# gps_and_sensor_20180111.net
KiCad netlist of a schematic drawn in EAGLE
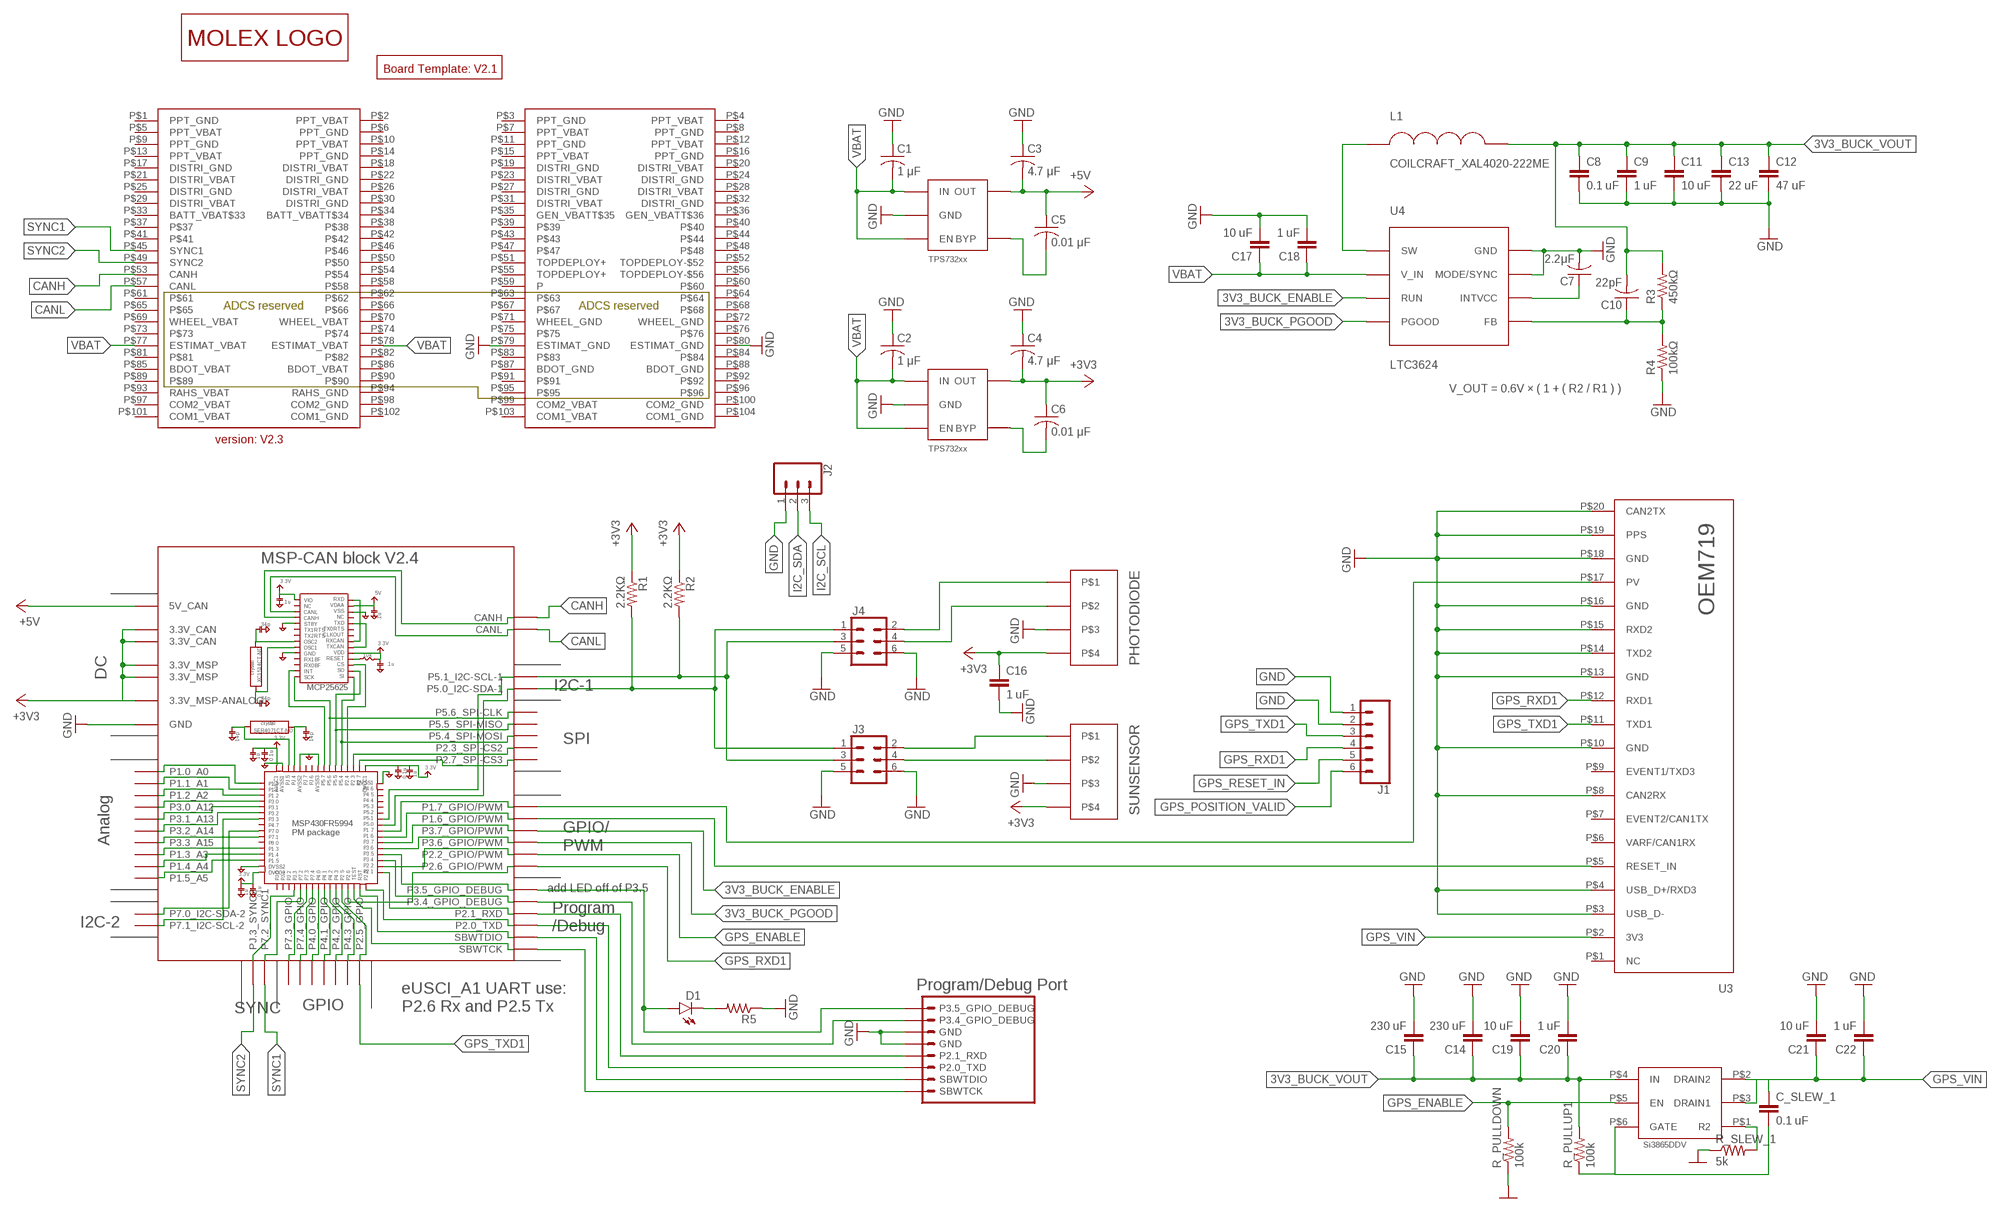
[diagram p0: schematic, sheet 1]

(export (version "E")
  (design (tool "Eeschema 10.0.6"))
  (components
    (comp (ref "B1")
      (value "BOARD_TEMPLATE1")
      (footprint "eagle-import:BOARD_TEMPLATE")
      (libsource (lib "eagle-import") (part "BOARD_TEMPLATE1"))
    )
    (comp (ref "BLK1")
      (value "MSP-CAN_BLOCK")
      (footprint "eagle-import:MSP-CAN_BLOCK")
      (libsource (lib "eagle-import") (part "MSP-CAN_BLOCK"))
    )
    (comp (ref "C1")
      (value "1 μF")
      (footprint "eagle-import:C0805")
      (libsource (lib "eagle-import") (part "C-USC0805"))
    )
    (comp (ref "C2")
      (value "1 μF")
      (footprint "eagle-import:C0805")
      (libsource (lib "eagle-import") (part "C-USC0805"))
    )
    (comp (ref "C3")
      (value "4.7 μF")
      (footprint "eagle-import:C0805")
      (libsource (lib "eagle-import") (part "C-USC0805"))
    )
    (comp (ref "C4")
      (value "4.7 μF")
      (footprint "eagle-import:C0805")
      (libsource (lib "eagle-import") (part "C-USC0805"))
    )
    (comp (ref "C5")
      (value "0.01 μF")
      (footprint "eagle-import:C0805")
      (libsource (lib "eagle-import") (part "C-USC0805"))
    )
    (comp (ref "C6")
      (value "0.01 μF")
      (footprint "eagle-import:C0805")
      (libsource (lib "eagle-import") (part "C-USC0805"))
    )
    (comp (ref "C7")
      (value "2.2μF")
      (footprint "eagle-import:C0805")
      (libsource (lib "eagle-import") (part "C-USC0805"))
    )
    (comp (ref "C8")
      (value "0.1 uF")
      (footprint "eagle-import:0805")
      (libsource (lib "eagle-import") (part "CAPACITOR0805"))
    )
    (comp (ref "C9")
      (value "1 uF")
      (footprint "eagle-import:0805")
      (libsource (lib "eagle-import") (part "CAPACITOR0805"))
    )
    (comp (ref "C10")
      (value "22pF")
      (footprint "eagle-import:C0805")
      (libsource (lib "eagle-import") (part "C-USC0805"))
    )
    (comp (ref "C11")
      (value "10 uF")
      (footprint "eagle-import:0805")
      (libsource (lib "eagle-import") (part "CAPACITOR0805"))
    )
    (comp (ref "C12")
      (value "47 uF")
      (footprint "eagle-import:1206")
      (libsource (lib "eagle-import") (part "CAPACITOR1206"))
    )
    (comp (ref "C13")
      (value "22 uF")
      (footprint "eagle-import:1206")
      (libsource (lib "eagle-import") (part "CAPACITOR1206"))
    )
    (comp (ref "C14")
      (value "230 uF")
      (footprint "eagle-import:PANASONIC_SVPG")
      (libsource (lib "eagle-import") (part "CAPACITORPANASONIC_16SVPG270M"))
    )
    (comp (ref "C15")
      (value "230 uF")
      (footprint "eagle-import:PANASONIC_SVPG")
      (libsource (lib "eagle-import") (part "CAPACITORPANASONIC_16SVPG270M"))
    )
    (comp (ref "C16")
      (value "1 uF")
      (footprint "eagle-import:0805")
      (libsource (lib "eagle-import") (part "CAPACITOR0805"))
    )
    (comp (ref "C17")
      (value "10 uF")
      (footprint "eagle-import:0805")
      (libsource (lib "eagle-import") (part "CAPACITOR0805"))
    )
    (comp (ref "C18")
      (value "1 uF")
      (footprint "eagle-import:0805")
      (libsource (lib "eagle-import") (part "CAPACITOR0805"))
    )
    (comp (ref "C19")
      (value "10 uF")
      (footprint "eagle-import:0805")
      (libsource (lib "eagle-import") (part "CAPACITOR0805"))
    )
    (comp (ref "C20")
      (value "1 uF")
      (footprint "eagle-import:0805")
      (libsource (lib "eagle-import") (part "CAPACITOR0805"))
    )
    (comp (ref "C21")
      (value "10 uF")
      (footprint "eagle-import:0805")
      (libsource (lib "eagle-import") (part "CAPACITOR0805"))
    )
    (comp (ref "C22")
      (value "1 uF")
      (footprint "eagle-import:0805")
      (libsource (lib "eagle-import") (part "CAPACITOR0805"))
    )
    (comp (ref "CONN1")
      (value "PC104_CONNECTOR")
      (footprint "eagle-import:PC104_CONNECTOR")
      (libsource (lib "eagle-import") (part "PC104_CONNECTOR"))
    )
    (comp (ref "C_SLEW_1")
      (value "0.1 uF")
      (footprint "eagle-import:0805")
      (libsource (lib "eagle-import") (part "CAPACITOR0805"))
    )
    (comp (ref "D1")
      (value "LED")
      (footprint "eagle-import:LED-1206")
      (libsource (lib "eagle-import") (part "LED"))
    )
    (comp (ref "J1")
      (value "CONN_06LOCK")
      (footprint "eagle-import:1X06_LOCK")
      (libsource (lib "eagle-import") (part "CONN_06LOCK"))
    )
    (comp (ref "J2")
      (value "CONN_03LOCK")
      (footprint "eagle-import:1X03_LOCK")
      (libsource (lib "eagle-import") (part "CONN_03LOCK"))
    )
    (comp (ref "J3")
      (value "CONN_03X22X3_SILK_MALE_PTH")
      (footprint "eagle-import:2X3")
      (libsource (lib "eagle-import") (part "CONN_03X22X3_SILK_MALE_PTH"))
    )
    (comp (ref "J4")
      (value "CONN_03X22X3_SILK_MALE_PTH")
      (footprint "eagle-import:2X3")
      (libsource (lib "eagle-import") (part "CONN_03X22X3_SILK_MALE_PTH"))
    )
    (comp (ref "L1")
      (value "COILCRAFT_XAL4020-222ME")
      (footprint "eagle-import:COILCRAFT_XAL4020")
      (libsource (lib "eagle-import") (part "COILCRAFT_XAL4020-222ME"))
    )
    (comp (ref "PHOTODIODE")
      (value "PICOLOCK_4")
      (footprint "eagle-import:PICOLOCK_4")
      (libsource (lib "eagle-import") (part "PICOLOCK_4"))
    )
    (comp (ref "R1")
      (value "2.2KΩ")
      (footprint "eagle-import:R0805")
      (libsource (lib "eagle-import") (part "R-US_R0805"))
    )
    (comp (ref "R2")
      (value "2.2KΩ")
      (footprint "eagle-import:R0805")
      (libsource (lib "eagle-import") (part "R-US_R0805"))
    )
    (comp (ref "R3")
      (value "450kΩ")
      (footprint "eagle-import:R0805")
      (libsource (lib "eagle-import") (part "R-US_R0805"))
    )
    (comp (ref "R4")
      (value "100kΩ")
      (footprint "eagle-import:R0805")
      (libsource (lib "eagle-import") (part "R-US_R0805"))
    )
    (comp (ref "R5")
      (value "RESISTOR0805")
      (footprint "eagle-import:0805")
      (libsource (lib "eagle-import") (part "RESISTOR0805"))
    )
    (comp (ref "R_PULLDOWN")
      (value "100k")
      (footprint "eagle-import:0805")
      (libsource (lib "eagle-import") (part "RESISTOR0805"))
    )
    (comp (ref "R_PULLUP1")
      (value "100k")
      (footprint "eagle-import:0805")
      (libsource (lib "eagle-import") (part "RESISTOR0805"))
    )
    (comp (ref "R_SLEW_1")
      (value "5k")
      (footprint "eagle-import:0805")
      (libsource (lib "eagle-import") (part "RESISTOR0805"))
    )
    (comp (ref "SUNSENSOR")
      (value "PICOLOCK_4")
      (footprint "eagle-import:PICOLOCK_4")
      (libsource (lib "eagle-import") (part "PICOLOCK_4"))
    )
    (comp (ref "U$1")
      (value "LOGO_MOLEX")
      (footprint "eagle-import:LOGO_MOLEX")
      (libsource (lib "eagle-import") (part "LOGO_MOLEX"))
    )
    (comp (ref "U$2")
      (value "PROGRAM/DEBUG_PORT")
      (footprint "eagle-import:1X08_CONNECTOR")
      (libsource (lib "eagle-import") (part "PROGRAM/DEBUG_PORT"))
    )
    (comp (ref "U$3")
      (value "SI3865DDV")
      (footprint "eagle-import:TSOP-6")
      (libsource (lib "eagle-import") (part "SI3865DDV"))
    )
    (comp (ref "U1")
      (value "TPS732XX")
      (footprint "eagle-import:SOT-23-5")
      (libsource (lib "eagle-import") (part "TPS732XX"))
    )
    (comp (ref "U2")
      (value "TPS732XX")
      (footprint "eagle-import:SOT-23-5")
      (libsource (lib "eagle-import") (part "TPS732XX"))
    )
    (comp (ref "U3")
      (value "OEM719")
      (footprint "eagle-import:OEM719")
      (libsource (lib "eagle-import") (part "OEM719"))
    )
    (comp (ref "U4")
      (value "LTC3624")
      (footprint "eagle-import:LTC3624")
      (libsource (lib "eagle-import") (part "LTC3624"))
    )
  )
  (nets
    (net (code "1") (name "+3V3") (class "Default")
      (node (ref "BLK1") (pin "3.3V@CAN1") (pinfunction "3.3V_CAN_3.3V@CAN1") (pintype "bidirectional"))
      (node (ref "BLK1") (pin "3.3V@CAN2") (pinfunction "3.3V_CAN_3.3V@CAN2") (pintype "bidirectional"))
      (node (ref "BLK1") (pin "3.3V@MSP1") (pinfunction "3.3V_MSP_3.3V@MSP1") (pintype "bidirectional"))
      (node (ref "BLK1") (pin "3.3V@MSP2") (pinfunction "3.3V_MSP_3.3V@MSP2") (pintype "bidirectional"))
      (node (ref "BLK1") (pin "3.3V_ANALOG@MSP2") (pinfunction "3.3V_MSP-ANALOG_3.3V_ANALOG@MSP2") (pintype "bidirectional"))
      (node (ref "C16") (pin "1") (pinfunction "1_1") (pintype "passive"))
      (node (ref "C4") (pin "2") (pinfunction "2_2") (pintype "passive"))
      (node (ref "C6") (pin "1") (pinfunction "1_1") (pintype "passive"))
      (node (ref "PHOTODIODE") (pin "P$4") (pinfunction "P$4_P$4") (pintype "bidirectional"))
      (node (ref "R1") (pin "1") (pinfunction "1_1") (pintype "passive"))
      (node (ref "R2") (pin "1") (pinfunction "1_1") (pintype "passive"))
      (node (ref "SUNSENSOR") (pin "P$4") (pinfunction "P$4_P$4") (pintype "bidirectional"))
      (node (ref "U2") (pin "P$5") (pinfunction "OUT_P$5") (pintype "bidirectional"))
    )
    (net (code "2") (name "+5V") (class "Default")
      (node (ref "BLK1") (pin "5V") (pinfunction "5V_CAN_5V") (pintype "bidirectional"))
      (node (ref "C3") (pin "2") (pinfunction "2_2") (pintype "passive"))
      (node (ref "C5") (pin "1") (pinfunction "1_1") (pintype "passive"))
      (node (ref "U1") (pin "P$5") (pinfunction "OUT_P$5") (pintype "bidirectional"))
    )
    (net (code "3") (name "3V3_BUCK_ENABLE") (class "Default")
      (node (ref "BLK1") (pin "P3.7_GPIO/PWM") (pinfunction "P3.7_GPIO/PWM_P3.7_GPIO/PWM") (pintype "bidirectional"))
      (node (ref "U4") (pin "RUN") (pinfunction "RUN_RUN") (pintype "bidirectional"))
    )
    (net (code "4") (name "3V3_BUCK_PGOOD") (class "Default")
      (node (ref "BLK1") (pin "P3.6_GPIO/PWM") (pinfunction "P3.6_GPIO/PWM_P3.6_GPIO/PWM") (pintype "bidirectional"))
      (node (ref "U4") (pin "PGOOD") (pinfunction "PGOOD_PGOOD") (pintype "bidirectional"))
    )
    (net (code "5") (name "3V3_BUCK_VOUT") (class "Default")
      (node (ref "C10") (pin "2") (pinfunction "2_2") (pintype "passive"))
      (node (ref "C11") (pin "1") (pinfunction "1_1") (pintype "passive"))
      (node (ref "C12") (pin "1") (pinfunction "1_1") (pintype "passive"))
      (node (ref "C13") (pin "1") (pinfunction "1_1") (pintype "passive"))
      (node (ref "C14") (pin "POS") (pinfunction "1_POS") (pintype "passive"))
      (node (ref "C15") (pin "POS") (pinfunction "1_POS") (pintype "passive"))
      (node (ref "C19") (pin "1") (pinfunction "1_1") (pintype "passive"))
      (node (ref "C20") (pin "1") (pinfunction "1_1") (pintype "passive"))
      (node (ref "C8") (pin "1") (pinfunction "1_1") (pintype "passive"))
      (node (ref "C9") (pin "1") (pinfunction "1_1") (pintype "passive"))
      (node (ref "L1") (pin "P$2") (pinfunction "P$2_P$2") (pintype "bidirectional"))
      (node (ref "R3") (pin "2") (pinfunction "2_2") (pintype "passive"))
      (node (ref "R_PULLUP1") (pin "2") (pinfunction "2_2") (pintype "passive"))
      (node (ref "U$3") (pin "P$4") (pinfunction "IN_P$4") (pintype "bidirectional"))
    )
    (net (code "6") (name "CANH") (class "Default")
      (node (ref "BLK1") (pin "CANH") (pinfunction "CANH_CANH") (pintype "bidirectional"))
      (node (ref "CONN1") (pin "P$53") (pinfunction "CANH_P$53") (pintype "bidirectional"))
    )
    (net (code "7") (name "CANL") (class "Default")
      (node (ref "BLK1") (pin "CANL") (pinfunction "CANL_CANL") (pintype "bidirectional"))
      (node (ref "CONN1") (pin "P$57") (pinfunction "CANL_P$57") (pintype "bidirectional"))
    )
    (net (code "8") (name "GND") (class "Default")
      (node (ref "BLK1") (pin "GND@1") (pinfunction "GND_GND@1") (pintype "bidirectional"))
      (node (ref "BLK1") (pin "GND@10") (pinfunction "GND_GND@10") (pintype "bidirectional"))
      (node (ref "BLK1") (pin "GND@11") (pinfunction "GND_GND@11") (pintype "bidirectional"))
      (node (ref "BLK1") (pin "GND@12") (pinfunction "GND_GND@12") (pintype "bidirectional"))
      (node (ref "BLK1") (pin "GND@13") (pinfunction "GND_GND@13") (pintype "bidirectional"))
      (node (ref "BLK1") (pin "GND@14") (pinfunction "GND_GND@14") (pintype "bidirectional"))
      (node (ref "BLK1") (pin "GND@15") (pinfunction "GND_GND@15") (pintype "bidirectional"))
      (node (ref "BLK1") (pin "GND@16") (pinfunction "GND_GND@16") (pintype "bidirectional"))
      (node (ref "BLK1") (pin "GND@17") (pinfunction "GND_GND@17") (pintype "bidirectional"))
      (node (ref "BLK1") (pin "GND@2") (pinfunction "GND_GND@2") (pintype "bidirectional"))
      (node (ref "BLK1") (pin "GND@26") (pinfunction "GND_GND@26") (pintype "bidirectional"))
      (node (ref "BLK1") (pin "GND@3") (pinfunction "GND_GND@3") (pintype "bidirectional"))
      (node (ref "BLK1") (pin "GND@4") (pinfunction "GND_GND@4") (pintype "bidirectional"))
      (node (ref "BLK1") (pin "GND@5") (pinfunction "GND_GND@5") (pintype "bidirectional"))
      (node (ref "BLK1") (pin "GND@7") (pinfunction "GND_GND@7") (pintype "bidirectional"))
      (node (ref "BLK1") (pin "GND@8") (pinfunction "GND_GND@8") (pintype "bidirectional"))
      (node (ref "BLK1") (pin "GND@9") (pinfunction "GND_GND@9") (pintype "bidirectional"))
      (node (ref "C1") (pin "1") (pinfunction "1_1") (pintype "passive"))
      (node (ref "C11") (pin "2") (pinfunction "2_2") (pintype "passive"))
      (node (ref "C12") (pin "2") (pinfunction "2_2") (pintype "passive"))
      (node (ref "C13") (pin "2") (pinfunction "2_2") (pintype "passive"))
      (node (ref "C14") (pin "NEG") (pinfunction "2_NEG") (pintype "passive"))
      (node (ref "C15") (pin "NEG") (pinfunction "2_NEG") (pintype "passive"))
      (node (ref "C16") (pin "2") (pinfunction "2_2") (pintype "passive"))
      (node (ref "C17") (pin "2") (pinfunction "2_2") (pintype "passive"))
      (node (ref "C18") (pin "2") (pinfunction "2_2") (pintype "passive"))
      (node (ref "C19") (pin "2") (pinfunction "2_2") (pintype "passive"))
      (node (ref "C2") (pin "1") (pinfunction "1_1") (pintype "passive"))
      (node (ref "C20") (pin "2") (pinfunction "2_2") (pintype "passive"))
      (node (ref "C21") (pin "2") (pinfunction "2_2") (pintype "passive"))
      (node (ref "C22") (pin "2") (pinfunction "2_2") (pintype "passive"))
      (node (ref "C3") (pin "1") (pinfunction "1_1") (pintype "passive"))
      (node (ref "C4") (pin "1") (pinfunction "1_1") (pintype "passive"))
      (node (ref "C7") (pin "2") (pinfunction "2_2") (pintype "passive"))
      (node (ref "C8") (pin "2") (pinfunction "2_2") (pintype "passive"))
      (node (ref "C9") (pin "2") (pinfunction "2_2") (pintype "passive"))
      (node (ref "CONN1") (pin "P$79") (pinfunction "ESTIMAT_GND_P$79") (pintype "bidirectional"))
      (node (ref "CONN1") (pin "P$80") (pinfunction "ESTIMAT_GND_P$80") (pintype "bidirectional"))
      (node (ref "J1") (pin "1") (pinfunction "1_1") (pintype "passive"))
      (node (ref "J1") (pin "2") (pinfunction "2_2") (pintype "passive"))
      (node (ref "J2") (pin "1") (pinfunction "1_1") (pintype "passive"))
      (node (ref "J3") (pin "5") (pinfunction "5_5") (pintype "bidirectional"))
      (node (ref "J3") (pin "6") (pinfunction "6_6") (pintype "bidirectional"))
      (node (ref "J4") (pin "5") (pinfunction "5_5") (pintype "bidirectional"))
      (node (ref "J4") (pin "6") (pinfunction "6_6") (pintype "bidirectional"))
      (node (ref "PHOTODIODE") (pin "P$3") (pinfunction "P$3_P$3") (pintype "bidirectional"))
      (node (ref "R4") (pin "1") (pinfunction "1_1") (pintype "passive"))
      (node (ref "R5") (pin "1") (pinfunction "1_1") (pintype "passive"))
      (node (ref "R_PULLDOWN") (pin "1") (pinfunction "1_1") (pintype "passive"))
      (node (ref "R_SLEW_1") (pin "1") (pinfunction "1_1") (pintype "passive"))
      (node (ref "SUNSENSOR") (pin "P$3") (pinfunction "P$3_P$3") (pintype "bidirectional"))
      (node (ref "U$2") (pin "5") (pinfunction "GND_5") (pintype "bidirectional"))
      (node (ref "U$2") (pin "6") (pinfunction "GND_6") (pintype "bidirectional"))
      (node (ref "U1") (pin "P$2") (pinfunction "GND_P$2") (pintype "bidirectional"))
      (node (ref "U2") (pin "P$2") (pinfunction "GND_P$2") (pintype "bidirectional"))
      (node (ref "U3") (pin "P$10") (pinfunction "GND_P$10") (pintype "bidirectional"))
      (node (ref "U3") (pin "P$13") (pinfunction "GND_P$13") (pintype "bidirectional"))
      (node (ref "U3") (pin "P$14") (pinfunction "TXD2_P$14") (pintype "bidirectional"))
      (node (ref "U3") (pin "P$15") (pinfunction "RXD2_P$15") (pintype "bidirectional"))
      (node (ref "U3") (pin "P$16") (pinfunction "GND_P$16") (pintype "bidirectional"))
      (node (ref "U3") (pin "P$18") (pinfunction "GND_P$18") (pintype "bidirectional"))
      (node (ref "U3") (pin "P$19") (pinfunction "PPS_P$19") (pintype "bidirectional"))
      (node (ref "U3") (pin "P$20") (pinfunction "CAN2TX_P$20") (pintype "bidirectional"))
      (node (ref "U3") (pin "P$3") (pinfunction "USB_D-_P$3") (pintype "bidirectional"))
      (node (ref "U3") (pin "P$4") (pinfunction "USB_D+/RXD3_P$4") (pintype "bidirectional"))
      (node (ref "U3") (pin "P$8") (pinfunction "CAN2RX_P$8") (pintype "bidirectional"))
      (node (ref "U4") (pin "GND@1") (pinfunction "GND_GND@1") (pintype "bidirectional"))
      (node (ref "U4") (pin "GND@PAD") (pinfunction "GND_GND@PAD") (pintype "bidirectional"))
      (node (ref "U4") (pin "MODE/SYNC") (pinfunction "MODE/SYNC_MODE/SYNC") (pintype "bidirectional"))
    )
    (net (code "9") (name "GPS_ENABLE") (class "Default")
      (node (ref "BLK1") (pin "P2.2_GPIO/PWM") (pinfunction "P2.2_GPIO/PWM_P2.2_GPIO/PWM") (pintype "bidirectional"))
      (node (ref "R_PULLDOWN") (pin "2") (pinfunction "2_2") (pintype "passive"))
      (node (ref "U$3") (pin "P$5") (pinfunction "EN_P$5") (pintype "bidirectional"))
    )
    (net (code "10") (name "GPS_POSITION_VALID") (class "Default")
      (node (ref "BLK1") (pin "P1.7_GPIO/PWM") (pinfunction "P1.7_GPIO/PWM_P1.7_GPIO/PWM") (pintype "bidirectional"))
      (node (ref "J1") (pin "6") (pinfunction "6_6") (pintype "passive"))
      (node (ref "U3") (pin "P$17") (pinfunction "PV_P$17") (pintype "bidirectional"))
    )
    (net (code "11") (name "GPS_RESET_IN") (class "Default")
      (node (ref "BLK1") (pin "P1.6_GPIO/PWM") (pinfunction "P1.6_GPIO/PWM_P1.6_GPIO/PWM") (pintype "bidirectional"))
      (node (ref "J1") (pin "5") (pinfunction "5_5") (pintype "passive"))
      (node (ref "U3") (pin "P$5") (pinfunction "RESET_IN_P$5") (pintype "bidirectional"))
    )
    (net (code "12") (name "GPS_RXD1") (class "Default")
      (node (ref "BLK1") (pin "P2.6_GPIO/PWM") (pinfunction "P2.6_GPIO/PWM_P2.6_GPIO/PWM") (pintype "bidirectional"))
      (node (ref "J1") (pin "4") (pinfunction "4_4") (pintype "passive"))
      (node (ref "U3") (pin "P$12") (pinfunction "RXD1_P$12") (pintype "bidirectional"))
    )
    (net (code "13") (name "GPS_TXD1") (class "Default")
      (node (ref "BLK1") (pin "P2.5_GPIO") (pinfunction "P2.5_GPIO_P2.5_GPIO") (pintype "bidirectional"))
      (node (ref "J1") (pin "3") (pinfunction "3_3") (pintype "passive"))
      (node (ref "U3") (pin "P$11") (pinfunction "TXD1_P$11") (pintype "bidirectional"))
    )
    (net (code "14") (name "GPS_VIN") (class "Default")
      (node (ref "C21") (pin "1") (pinfunction "1_1") (pintype "passive"))
      (node (ref "C22") (pin "1") (pinfunction "1_1") (pintype "passive"))
      (node (ref "C_SLEW_1") (pin "1") (pinfunction "1_1") (pintype "passive"))
      (node (ref "U$3") (pin "P$2") (pinfunction "DRAIN2_P$2") (pintype "bidirectional"))
      (node (ref "U$3") (pin "P$3") (pinfunction "DRAIN1_P$3") (pintype "bidirectional"))
      (node (ref "U3") (pin "P$2") (pinfunction "3V3_P$2") (pintype "bidirectional"))
    )
    (net (code "15") (name "I2C_SCL") (class "Default")
      (node (ref "BLK1") (pin "P5.1_I2C-SCL-1") (pinfunction "P5.1_I2C-SCL-1_P5.1_I2C-SCL-1") (pintype "bidirectional"))
      (node (ref "J2") (pin "3") (pinfunction "3_3") (pintype "passive"))
      (node (ref "J3") (pin "3") (pinfunction "3_3") (pintype "bidirectional"))
      (node (ref "J4") (pin "3") (pinfunction "3_3") (pintype "bidirectional"))
      (node (ref "R2") (pin "2") (pinfunction "2_2") (pintype "passive"))
    )
    (net (code "16") (name "I2C_SDA") (class "Default")
      (node (ref "BLK1") (pin "P5.0_I2C-SDA-1") (pinfunction "P5.0_I2C-SDA-1_P5.0_I2C-SDA-1") (pintype "bidirectional"))
      (node (ref "J2") (pin "2") (pinfunction "2_2") (pintype "passive"))
      (node (ref "J3") (pin "1") (pinfunction "1_1") (pintype "bidirectional"))
      (node (ref "J4") (pin "1") (pinfunction "1_1") (pintype "bidirectional"))
      (node (ref "R1") (pin "2") (pinfunction "2_2") (pintype "passive"))
    )
    (net (code "17") (name "Net-(BLK1-PadSBWTCK)") (class "Default")
      (node (ref "BLK1") (pin "SBWTCK") (pinfunction "SBWTCK_SBWTCK") (pintype "bidirectional"))
      (node (ref "U$2") (pin "SBWTCK") (pinfunction "SBWTCK_SBWTCK") (pintype "bidirectional"))
    )
    (net (code "18") (name "Net-(C7-Pad1)") (class "Default")
      (node (ref "C7") (pin "1") (pinfunction "1_1") (pintype "passive"))
      (node (ref "U4") (pin "INTVCC") (pinfunction "INTVCC_INTVCC") (pintype "bidirectional"))
    )
    (net (code "19") (name "Net-(C10-Pad1)") (class "Default")
      (node (ref "C10") (pin "1") (pinfunction "1_1") (pintype "passive"))
      (node (ref "R3") (pin "1") (pinfunction "1_1") (pintype "passive"))
      (node (ref "R4") (pin "2") (pinfunction "2_2") (pintype "passive"))
      (node (ref "U4") (pin "FB") (pinfunction "FB_FB") (pintype "bidirectional"))
    )
    (net (code "20") (name "Net-(D1-PadC)") (class "Default")
      (node (ref "D1") (pin "C") (pinfunction "C_C") (pintype "passive"))
      (node (ref "R5") (pin "2") (pinfunction "2_2") (pintype "passive"))
    )
    (net (code "21") (name "Net-(J3-Pad2)") (class "Default")
      (node (ref "J3") (pin "2") (pinfunction "2_2") (pintype "bidirectional"))
      (node (ref "SUNSENSOR") (pin "P$1") (pinfunction "P$1_P$1") (pintype "bidirectional"))
    )
    (net (code "22") (name "Net-(J3-Pad4)") (class "Default")
      (node (ref "J3") (pin "4") (pinfunction "4_4") (pintype "bidirectional"))
      (node (ref "SUNSENSOR") (pin "P$2") (pinfunction "P$2_P$2") (pintype "bidirectional"))
    )
    (net (code "23") (name "Net-(J4-Pad2)") (class "Default")
      (node (ref "J4") (pin "2") (pinfunction "2_2") (pintype "bidirectional"))
      (node (ref "PHOTODIODE") (pin "P$1") (pinfunction "P$1_P$1") (pintype "bidirectional"))
    )
    (net (code "24") (name "Net-(J4-Pad4)") (class "Default")
      (node (ref "J4") (pin "4") (pinfunction "4_4") (pintype "bidirectional"))
      (node (ref "PHOTODIODE") (pin "P$2") (pinfunction "P$2_P$2") (pintype "bidirectional"))
    )
    (net (code "25") (name "Net-(L1-PadP$1)") (class "Default")
      (node (ref "L1") (pin "P$1") (pinfunction "P$1_P$1") (pintype "bidirectional"))
      (node (ref "U4") (pin "SW") (pinfunction "SW_SW") (pintype "bidirectional"))
    )
    (net (code "26") (name "Net-(U$2-P2.0_TXD)") (class "Default")
      (node (ref "BLK1") (pin "P2.0_TXD") (pinfunction "P2.0_TXD_P2.0_TXD") (pintype "bidirectional"))
      (node (ref "U$2") (pin "3") (pinfunction "P2.0_TXD_3") (pintype "bidirectional"))
    )
    (net (code "27") (name "Net-(U$2-P2.1_RXD)") (class "Default")
      (node (ref "BLK1") (pin "P2.1_RXD") (pinfunction "P2.1_RXD_P2.1_RXD") (pintype "bidirectional"))
      (node (ref "U$2") (pin "4") (pinfunction "P2.1_RXD_4") (pintype "bidirectional"))
    )
    (net (code "28") (name "Net-(U$2-P3.4_GPIO_DEBUG)") (class "Default")
      (node (ref "BLK1") (pin "P3.4_GPIO_DEBUG") (pinfunction "P3.4_GPIO_DEBUG_P3.4_GPIO_DEBUG") (pintype "bidirectional"))
      (node (ref "U$2") (pin "7") (pinfunction "P3.4_GPIO_DEBUG_7") (pintype "bidirectional"))
    )
    (net (code "29") (name "Net-(U$2-P3.5_GPIO_DEBUG)") (class "Default")
      (node (ref "BLK1") (pin "P3.5_GPIO_DEBUG") (pinfunction "P3.5_GPIO_DEBUG_P3.5_GPIO_DEBUG") (pintype "bidirectional"))
      (node (ref "D1") (pin "A") (pinfunction "A_A") (pintype "passive"))
      (node (ref "U$2") (pin "8") (pinfunction "P3.5_GPIO_DEBUG_8") (pintype "bidirectional"))
    )
    (net (code "30") (name "Net-(U$2-SBWTDIO)") (class "Default")
      (node (ref "BLK1") (pin "SBWTDIO") (pinfunction "SBWTDIO_SBWTDIO") (pintype "bidirectional"))
      (node (ref "U$2") (pin "2") (pinfunction "SBWTDIO_2") (pintype "bidirectional"))
    )
    (net (code "31") (name "Net-(U$3-GATE)") (class "Default")
      (node (ref "C_SLEW_1") (pin "2") (pinfunction "2_2") (pintype "passive"))
      (node (ref "R_PULLUP1") (pin "1") (pinfunction "1_1") (pintype "passive"))
      (node (ref "U$3") (pin "P$6") (pinfunction "GATE_P$6") (pintype "bidirectional"))
    )
    (net (code "32") (name "Net-(U$3-R2)") (class "Default")
      (node (ref "R_SLEW_1") (pin "2") (pinfunction "2_2") (pintype "passive"))
      (node (ref "U$3") (pin "P$1") (pinfunction "R2_P$1") (pintype "bidirectional"))
    )
    (net (code "33") (name "Net-(U1-BYP)") (class "Default")
      (node (ref "C5") (pin "2") (pinfunction "2_2") (pintype "passive"))
      (node (ref "U1") (pin "P$4") (pinfunction "BYP_P$4") (pintype "bidirectional"))
    )
    (net (code "34") (name "Net-(U2-BYP)") (class "Default")
      (node (ref "C6") (pin "2") (pinfunction "2_2") (pintype "passive"))
      (node (ref "U2") (pin "P$4") (pinfunction "BYP_P$4") (pintype "bidirectional"))
    )
    (net (code "35") (name "SYNC1") (class "Default")
      (node (ref "BLK1") (pin "P7.2_SYNC1") (pinfunction "P7.2_SYNC1_P7.2_SYNC1") (pintype "bidirectional"))
      (node (ref "CONN1") (pin "P$45") (pinfunction "SYNC1_P$45") (pintype "bidirectional"))
    )
    (net (code "36") (name "SYNC2") (class "Default")
      (node (ref "BLK1") (pin "PJ.3_SYNC2") (pinfunction "PJ.3_SYNC2_PJ.3_SYNC2") (pintype "bidirectional"))
      (node (ref "CONN1") (pin "P$49") (pinfunction "SYNC2_P$49") (pintype "bidirectional"))
    )
    (net (code "37") (name "VBAT") (class "Default")
      (node (ref "C1") (pin "2") (pinfunction "2_2") (pintype "passive"))
      (node (ref "C17") (pin "1") (pinfunction "1_1") (pintype "passive"))
      (node (ref "C18") (pin "1") (pinfunction "1_1") (pintype "passive"))
      (node (ref "C2") (pin "2") (pinfunction "2_2") (pintype "passive"))
      (node (ref "CONN1") (pin "P$77") (pinfunction "ESTIMAT_VBAT_P$77") (pintype "bidirectional"))
      (node (ref "CONN1") (pin "P$78") (pinfunction "ESTIMAT_VBAT_P$78") (pintype "bidirectional"))
      (node (ref "U1") (pin "P$1") (pinfunction "IN_P$1") (pintype "bidirectional"))
      (node (ref "U1") (pin "P$3") (pinfunction "EN_P$3") (pintype "bidirectional"))
      (node (ref "U2") (pin "P$1") (pinfunction "IN_P$1") (pintype "bidirectional"))
      (node (ref "U2") (pin "P$3") (pinfunction "EN_P$3") (pintype "bidirectional"))
      (node (ref "U4") (pin "V_IN") (pinfunction "V_IN_V_IN") (pintype "bidirectional"))
    )
    (net (code "38") (name "unconnected-(BLK1-P2.3_SPI-CS2-PadP2.4_SPI-CS2)") (class "Default")
      (node (ref "BLK1") (pin "P2.4_SPI-CS2") (pinfunction "P2.3_SPI-CS2_P2.4_SPI-CS2") (pintype "bidirectional"))
    )
    (net (code "39") (name "unconnected-(BLK1-PadP1.0_A0)") (class "Default")
      (node (ref "BLK1") (pin "P1.0_A0") (pinfunction "P1.0_A0_P1.0_A0") (pintype "bidirectional"))
    )
    (net (code "40") (name "unconnected-(BLK1-PadP1.1_A1)") (class "Default")
      (node (ref "BLK1") (pin "P1.1_A1") (pinfunction "P1.1_A1_P1.1_A1") (pintype "bidirectional"))
    )
    (net (code "41") (name "unconnected-(BLK1-PadP1.2_A2)") (class "Default")
      (node (ref "BLK1") (pin "P1.2_A2") (pinfunction "P1.2_A2_P1.2_A2") (pintype "bidirectional"))
    )
    (net (code "42") (name "unconnected-(BLK1-PadP1.3_A3)") (class "Default")
      (node (ref "BLK1") (pin "P1.3_A3") (pinfunction "P1.3_A3_P1.3_A3") (pintype "bidirectional"))
    )
    (net (code "43") (name "unconnected-(BLK1-PadP1.4_A4)") (class "Default")
      (node (ref "BLK1") (pin "P1.4_A4") (pinfunction "P1.4_A4_P1.4_A4") (pintype "bidirectional"))
    )
    (net (code "44") (name "unconnected-(BLK1-PadP1.5_A5)") (class "Default")
      (node (ref "BLK1") (pin "P1.5_A5") (pinfunction "P1.5_A5_P1.5_A5") (pintype "bidirectional"))
    )
    (net (code "45") (name "unconnected-(BLK1-PadP2.7_SPI-CS3)") (class "Default")
      (node (ref "BLK1") (pin "P2.7_SPI-CS3") (pinfunction "P2.7_SPI-CS3_P2.7_SPI-CS3") (pintype "bidirectional"))
    )
    (net (code "46") (name "unconnected-(BLK1-PadP3.0_A12)") (class "Default")
      (node (ref "BLK1") (pin "P3.0_A12") (pinfunction "P3.0_A12_P3.0_A12") (pintype "bidirectional"))
    )
    (net (code "47") (name "unconnected-(BLK1-PadP3.1_A13)") (class "Default")
      (node (ref "BLK1") (pin "P3.1_A13") (pinfunction "P3.1_A13_P3.1_A13") (pintype "bidirectional"))
    )
    (net (code "48") (name "unconnected-(BLK1-PadP3.2_A14)") (class "Default")
      (node (ref "BLK1") (pin "P3.2_A14") (pinfunction "P3.2_A14_P3.2_A14") (pintype "bidirectional"))
    )
    (net (code "49") (name "unconnected-(BLK1-PadP3.3_A15)") (class "Default")
      (node (ref "BLK1") (pin "P3.3_A15") (pinfunction "P3.3_A15_P3.3_A15") (pintype "bidirectional"))
    )
    (net (code "50") (name "unconnected-(BLK1-PadP4.0_GPIO)") (class "Default")
      (node (ref "BLK1") (pin "P4.0_GPIO") (pinfunction "P4.0_GPIO_P4.0_GPIO") (pintype "bidirectional"))
    )
    (net (code "51") (name "unconnected-(BLK1-PadP4.1_GPIO)") (class "Default")
      (node (ref "BLK1") (pin "P4.1_GPIO") (pinfunction "P4.1_GPIO_P4.1_GPIO") (pintype "bidirectional"))
    )
    (net (code "52") (name "unconnected-(BLK1-PadP4.2_GPIO)") (class "Default")
      (node (ref "BLK1") (pin "P4.2_GPIO") (pinfunction "P4.2_GPIO_P4.2_GPIO") (pintype "bidirectional"))
    )
    (net (code "53") (name "unconnected-(BLK1-PadP4.3_GPIO)") (class "Default")
      (node (ref "BLK1") (pin "P4.3_GPIO") (pinfunction "P4.3_GPIO_P4.3_GPIO") (pintype "bidirectional"))
    )
    (net (code "54") (name "unconnected-(BLK1-PadP5.4_SPI-MOSI)") (class "Default")
      (node (ref "BLK1") (pin "P5.4_SPI-MOSI") (pinfunction "P5.4_SPI-MOSI_P5.4_SPI-MOSI") (pintype "bidirectional"))
    )
    (net (code "55") (name "unconnected-(BLK1-PadP5.5_SPI-MISO)") (class "Default")
      (node (ref "BLK1") (pin "P5.5_SPI-MISO") (pinfunction "P5.5_SPI-MISO_P5.5_SPI-MISO") (pintype "bidirectional"))
    )
    (net (code "56") (name "unconnected-(BLK1-PadP5.6_SPI-CLK)") (class "Default")
      (node (ref "BLK1") (pin "P5.6_SPI-CLK") (pinfunction "P5.6_SPI-CLK_P5.6_SPI-CLK") (pintype "bidirectional"))
    )
    (net (code "57") (name "unconnected-(BLK1-PadP7.0_I2C-SDA-2)") (class "Default")
      (node (ref "BLK1") (pin "P7.0_I2C-SDA-2") (pinfunction "P7.0_I2C-SDA-2_P7.0_I2C-SDA-2") (pintype "bidirectional"))
    )
    (net (code "58") (name "unconnected-(BLK1-PadP7.1_I2C-SCL-2)") (class "Default")
      (node (ref "BLK1") (pin "P7.1_I2C-SCL-2") (pinfunction "P7.1_I2C-SCL-2_P7.1_I2C-SCL-2") (pintype "bidirectional"))
    )
    (net (code "59") (name "unconnected-(BLK1-PadP7.3_GPIO)") (class "Default")
      (node (ref "BLK1") (pin "P7.3_GPIO") (pinfunction "P7.3_GPIO_P7.3_GPIO") (pintype "bidirectional"))
    )
    (net (code "60") (name "unconnected-(BLK1-PadP7.4_GPIO)") (class "Default")
      (node (ref "BLK1") (pin "P7.4_GPIO") (pinfunction "P7.4_GPIO_P7.4_GPIO") (pintype "bidirectional"))
    )
    (net (code "61") (name "unconnected-(CONN1-BATT_VBAT$33-PadP$33)") (class "Default")
      (node (ref "CONN1") (pin "P$33") (pinfunction "BATT_VBAT$33_P$33") (pintype "bidirectional"))
    )
    (net (code "62") (name "unconnected-(CONN1-BATT_VBATT$34-PadP$34)") (class "Default")
      (node (ref "CONN1") (pin "P$34") (pinfunction "BATT_VBATT$34_P$34") (pintype "bidirectional"))
    )
    (net (code "63") (name "unconnected-(CONN1-BDOT_GND-PadP$87)") (class "Default")
      (node (ref "CONN1") (pin "P$87") (pinfunction "BDOT_GND_P$87") (pintype "bidirectional"))
    )
    (net (code "64") (name "unconnected-(CONN1-BDOT_GND-PadP$88)") (class "Default")
      (node (ref "CONN1") (pin "P$88") (pinfunction "BDOT_GND_P$88") (pintype "bidirectional"))
    )
    (net (code "65") (name "unconnected-(CONN1-BDOT_VBAT-PadP$85)") (class "Default")
      (node (ref "CONN1") (pin "P$85") (pinfunction "BDOT_VBAT_P$85") (pintype "bidirectional"))
    )
    (net (code "66") (name "unconnected-(CONN1-BDOT_VBAT-PadP$86)") (class "Default")
      (node (ref "CONN1") (pin "P$86") (pinfunction "BDOT_VBAT_P$86") (pintype "bidirectional"))
    )
    (net (code "67") (name "unconnected-(CONN1-COM1_GND-PadP$102)") (class "Default")
      (node (ref "CONN1") (pin "P$102") (pinfunction "COM1_GND_P$102") (pintype "bidirectional"))
    )
    (net (code "68") (name "unconnected-(CONN1-COM1_GND-PadP$104)") (class "Default")
      (node (ref "CONN1") (pin "P$104") (pinfunction "COM1_GND_P$104") (pintype "bidirectional"))
    )
    (net (code "69") (name "unconnected-(CONN1-COM1_VBAT-PadP$101)") (class "Default")
      (node (ref "CONN1") (pin "P$101") (pinfunction "COM1_VBAT_P$101") (pintype "bidirectional"))
    )
    (net (code "70") (name "unconnected-(CONN1-COM1_VBAT-PadP$103)") (class "Default")
      (node (ref "CONN1") (pin "P$103") (pinfunction "COM1_VBAT_P$103") (pintype "bidirectional"))
    )
    (net (code "71") (name "unconnected-(CONN1-COM2_GND-PadP$98)") (class "Default")
      (node (ref "CONN1") (pin "P$98") (pinfunction "COM2_GND_P$98") (pintype "bidirectional"))
    )
    (net (code "72") (name "unconnected-(CONN1-COM2_GND-PadP$100)") (class "Default")
      (node (ref "CONN1") (pin "P$100") (pinfunction "COM2_GND_P$100") (pintype "bidirectional"))
    )
    (net (code "73") (name "unconnected-(CONN1-COM2_VBAT-PadP$97)") (class "Default")
      (node (ref "CONN1") (pin "P$97") (pinfunction "COM2_VBAT_P$97") (pintype "bidirectional"))
    )
    (net (code "74") (name "unconnected-(CONN1-COM2_VBAT-PadP$99)") (class "Default")
      (node (ref "CONN1") (pin "P$99") (pinfunction "COM2_VBAT_P$99") (pintype "bidirectional"))
    )
    (net (code "75") (name "unconnected-(CONN1-DISTRI_GND-PadP$17)") (class "Default")
      (node (ref "CONN1") (pin "P$17") (pinfunction "DISTRI_GND_P$17") (pintype "bidirectional"))
    )
    (net (code "76") (name "unconnected-(CONN1-DISTRI_GND-PadP$19)") (class "Default")
      (node (ref "CONN1") (pin "P$19") (pinfunction "DISTRI_GND_P$19") (pintype "bidirectional"))
    )
    (net (code "77") (name "unconnected-(CONN1-DISTRI_GND-PadP$22)") (class "Default")
      (node (ref "CONN1") (pin "P$22") (pinfunction "DISTRI_GND_P$22") (pintype "bidirectional"))
    )
    (net (code "78") (name "unconnected-(CONN1-DISTRI_GND-PadP$24)") (class "Default")
      (node (ref "CONN1") (pin "P$24") (pinfunction "DISTRI_GND_P$24") (pintype "bidirectional"))
    )
    (net (code "79") (name "unconnected-(CONN1-DISTRI_GND-PadP$25)") (class "Default")
      (node (ref "CONN1") (pin "P$25") (pinfunction "DISTRI_GND_P$25") (pintype "bidirectional"))
    )
    (net (code "80") (name "unconnected-(CONN1-DISTRI_GND-PadP$27)") (class "Default")
      (node (ref "CONN1") (pin "P$27") (pinfunction "DISTRI_GND_P$27") (pintype "bidirectional"))
    )
    (net (code "81") (name "unconnected-(CONN1-DISTRI_GND-PadP$30)") (class "Default")
      (node (ref "CONN1") (pin "P$30") (pinfunction "DISTRI_GND_P$30") (pintype "bidirectional"))
    )
    (net (code "82") (name "unconnected-(CONN1-DISTRI_GND-PadP$32)") (class "Default")
      (node (ref "CONN1") (pin "P$32") (pinfunction "DISTRI_GND_P$32") (pintype "bidirectional"))
    )
    (net (code "83") (name "unconnected-(CONN1-DISTRI_VBAT-PadP$18)") (class "Default")
      (node (ref "CONN1") (pin "P$18") (pinfunction "DISTRI_VBAT_P$18") (pintype "bidirectional"))
    )
    (net (code "84") (name "unconnected-(CONN1-DISTRI_VBAT-PadP$20)") (class "Default")
      (node (ref "CONN1") (pin "P$20") (pinfunction "DISTRI_VBAT_P$20") (pintype "bidirectional"))
    )
    (net (code "85") (name "unconnected-(CONN1-DISTRI_VBAT-PadP$21)") (class "Default")
      (node (ref "CONN1") (pin "P$21") (pinfunction "DISTRI_VBAT_P$21") (pintype "bidirectional"))
    )
    (net (code "86") (name "unconnected-(CONN1-DISTRI_VBAT-PadP$23)") (class "Default")
      (node (ref "CONN1") (pin "P$23") (pinfunction "DISTRI_VBAT_P$23") (pintype "bidirectional"))
    )
    (net (code "87") (name "unconnected-(CONN1-DISTRI_VBAT-PadP$26)") (class "Default")
      (node (ref "CONN1") (pin "P$26") (pinfunction "DISTRI_VBAT_P$26") (pintype "bidirectional"))
    )
    (net (code "88") (name "unconnected-(CONN1-DISTRI_VBAT-PadP$28)") (class "Default")
      (node (ref "CONN1") (pin "P$28") (pinfunction "DISTRI_VBAT_P$28") (pintype "bidirectional"))
    )
    (net (code "89") (name "unconnected-(CONN1-DISTRI_VBAT-PadP$29)") (class "Default")
      (node (ref "CONN1") (pin "P$29") (pinfunction "DISTRI_VBAT_P$29") (pintype "bidirectional"))
    )
    (net (code "90") (name "unconnected-(CONN1-DISTRI_VBAT-PadP$31)") (class "Default")
      (node (ref "CONN1") (pin "P$31") (pinfunction "DISTRI_VBAT_P$31") (pintype "bidirectional"))
    )
    (net (code "91") (name "unconnected-(CONN1-GEN_VBATT$35-PadP$35)") (class "Default")
      (node (ref "CONN1") (pin "P$35") (pinfunction "GEN_VBATT$35_P$35") (pintype "bidirectional"))
    )
    (net (code "92") (name "unconnected-(CONN1-GEN_VBATT$36-PadP$36)") (class "Default")
      (node (ref "CONN1") (pin "P$36") (pinfunction "GEN_VBATT$36_P$36") (pintype "bidirectional"))
    )
    (net (code "93") (name "unconnected-(CONN1-P-PadP$59)") (class "Default")
      (node (ref "CONN1") (pin "P$59") (pinfunction "P_P$59") (pintype "bidirectional"))
    )
    (net (code "94") (name "unconnected-(CONN1-PPT_GND-PadP$1)") (class "Default")
      (node (ref "CONN1") (pin "P$1") (pinfunction "PPT_GND_P$1") (pintype "bidirectional"))
    )
    (net (code "95") (name "unconnected-(CONN1-PPT_GND-PadP$3)") (class "Default")
      (node (ref "CONN1") (pin "P$3") (pinfunction "PPT_GND_P$3") (pintype "bidirectional"))
    )
    (net (code "96") (name "unconnected-(CONN1-PPT_GND-PadP$6)") (class "Default")
      (node (ref "CONN1") (pin "P$6") (pinfunction "PPT_GND_P$6") (pintype "bidirectional"))
    )
    (net (code "97") (name "unconnected-(CONN1-PPT_GND-PadP$8)") (class "Default")
      (node (ref "CONN1") (pin "P$8") (pinfunction "PPT_GND_P$8") (pintype "bidirectional"))
    )
    (net (code "98") (name "unconnected-(CONN1-PPT_GND-PadP$9)") (class "Default")
      (node (ref "CONN1") (pin "P$9") (pinfunction "PPT_GND_P$9") (pintype "bidirectional"))
    )
    (net (code "99") (name "unconnected-(CONN1-PPT_GND-PadP$11)") (class "Default")
      (node (ref "CONN1") (pin "P$11") (pinfunction "PPT_GND_P$11") (pintype "bidirectional"))
    )
    (net (code "100") (name "unconnected-(CONN1-PPT_GND-PadP$14)") (class "Default")
      (node (ref "CONN1") (pin "P$14") (pinfunction "PPT_GND_P$14") (pintype "bidirectional"))
    )
    (net (code "101") (name "unconnected-(CONN1-PPT_GND-PadP$16)") (class "Default")
      (node (ref "CONN1") (pin "P$16") (pinfunction "PPT_GND_P$16") (pintype "bidirectional"))
    )
    (net (code "102") (name "unconnected-(CONN1-PPT_VBAT-PadP$2)") (class "Default")
      (node (ref "CONN1") (pin "P$2") (pinfunction "PPT_VBAT_P$2") (pintype "bidirectional"))
    )
    (net (code "103") (name "unconnected-(CONN1-PPT_VBAT-PadP$4)") (class "Default")
      (node (ref "CONN1") (pin "P$4") (pinfunction "PPT_VBAT_P$4") (pintype "bidirectional"))
    )
    (net (code "104") (name "unconnected-(CONN1-PPT_VBAT-PadP$5)") (class "Default")
      (node (ref "CONN1") (pin "P$5") (pinfunction "PPT_VBAT_P$5") (pintype "bidirectional"))
    )
    (net (code "105") (name "unconnected-(CONN1-PPT_VBAT-PadP$7)") (class "Default")
      (node (ref "CONN1") (pin "P$7") (pinfunction "PPT_VBAT_P$7") (pintype "bidirectional"))
    )
    (net (code "106") (name "unconnected-(CONN1-PPT_VBAT-PadP$10)") (class "Default")
      (node (ref "CONN1") (pin "P$10") (pinfunction "PPT_VBAT_P$10") (pintype "bidirectional"))
    )
    (net (code "107") (name "unconnected-(CONN1-PPT_VBAT-PadP$12)") (class "Default")
      (node (ref "CONN1") (pin "P$12") (pinfunction "PPT_VBAT_P$12") (pintype "bidirectional"))
    )
    (net (code "108") (name "unconnected-(CONN1-PPT_VBAT-PadP$13)") (class "Default")
      (node (ref "CONN1") (pin "P$13") (pinfunction "PPT_VBAT_P$13") (pintype "bidirectional"))
    )
    (net (code "109") (name "unconnected-(CONN1-PPT_VBAT-PadP$15)") (class "Default")
      (node (ref "CONN1") (pin "P$15") (pinfunction "PPT_VBAT_P$15") (pintype "bidirectional"))
    )
    (net (code "110") (name "unconnected-(CONN1-PadP$37)") (class "Default")
      (node (ref "CONN1") (pin "P$37") (pinfunction "P$37_P$37") (pintype "bidirectional"))
    )
    (net (code "111") (name "unconnected-(CONN1-PadP$38)") (class "Default")
      (node (ref "CONN1") (pin "P$38") (pinfunction "P$38_P$38") (pintype "bidirectional"))
    )
    (net (code "112") (name "unconnected-(CONN1-PadP$39)") (class "Default")
      (node (ref "CONN1") (pin "P$39") (pinfunction "P$39_P$39") (pintype "bidirectional"))
    )
    (net (code "113") (name "unconnected-(CONN1-PadP$40)") (class "Default")
      (node (ref "CONN1") (pin "P$40") (pinfunction "P$40_P$40") (pintype "bidirectional"))
    )
    (net (code "114") (name "unconnected-(CONN1-PadP$41)") (class "Default")
      (node (ref "CONN1") (pin "P$41") (pinfunction "P$41_P$41") (pintype "bidirectional"))
    )
    (net (code "115") (name "unconnected-(CONN1-PadP$42)") (class "Default")
      (node (ref "CONN1") (pin "P$42") (pinfunction "P$42_P$42") (pintype "bidirectional"))
    )
    (net (code "116") (name "unconnected-(CONN1-PadP$43)") (class "Default")
      (node (ref "CONN1") (pin "P$43") (pinfunction "P$43_P$43") (pintype "bidirectional"))
    )
    (net (code "117") (name "unconnected-(CONN1-PadP$44)") (class "Default")
      (node (ref "CONN1") (pin "P$44") (pinfunction "P$44_P$44") (pintype "bidirectional"))
    )
    (net (code "118") (name "unconnected-(CONN1-PadP$46)") (class "Default")
      (node (ref "CONN1") (pin "P$46") (pinfunction "P$46_P$46") (pintype "bidirectional"))
    )
    (net (code "119") (name "unconnected-(CONN1-PadP$47)") (class "Default")
      (node (ref "CONN1") (pin "P$47") (pinfunction "P$47_P$47") (pintype "bidirectional"))
    )
    (net (code "120") (name "unconnected-(CONN1-PadP$48)") (class "Default")
      (node (ref "CONN1") (pin "P$48") (pinfunction "P$48_P$48") (pintype "bidirectional"))
    )
    (net (code "121") (name "unconnected-(CONN1-PadP$50)") (class "Default")
      (node (ref "CONN1") (pin "P$50") (pinfunction "P$50_P$50") (pintype "bidirectional"))
    )
    (net (code "122") (name "unconnected-(CONN1-PadP$54)") (class "Default")
      (node (ref "CONN1") (pin "P$54") (pinfunction "P$54_P$54") (pintype "bidirectional"))
    )
    (net (code "123") (name "unconnected-(CONN1-PadP$58)") (class "Default")
      (node (ref "CONN1") (pin "P$58") (pinfunction "P$58_P$58") (pintype "bidirectional"))
    )
    (net (code "124") (name "unconnected-(CONN1-PadP$60)") (class "Default")
      (node (ref "CONN1") (pin "P$60") (pinfunction "P$60_P$60") (pintype "bidirectional"))
    )
    (net (code "125") (name "unconnected-(CONN1-PadP$61)") (class "Default")
      (node (ref "CONN1") (pin "P$61") (pinfunction "P$61_P$61") (pintype "bidirectional"))
    )
    (net (code "126") (name "unconnected-(CONN1-PadP$62)") (class "Default")
      (node (ref "CONN1") (pin "P$62") (pinfunction "P$62_P$62") (pintype "bidirectional"))
    )
    (net (code "127") (name "unconnected-(CONN1-PadP$63)") (class "Default")
      (node (ref "CONN1") (pin "P$63") (pinfunction "P$63_P$63") (pintype "bidirectional"))
    )
    (net (code "128") (name "unconnected-(CONN1-PadP$64)") (class "Default")
      (node (ref "CONN1") (pin "P$64") (pinfunction "P$64_P$64") (pintype "bidirectional"))
    )
    (net (code "129") (name "unconnected-(CONN1-PadP$65)") (class "Default")
      (node (ref "CONN1") (pin "P$65") (pinfunction "P$65_P$65") (pintype "bidirectional"))
    )
    (net (code "130") (name "unconnected-(CONN1-PadP$66)") (class "Default")
      (node (ref "CONN1") (pin "P$66") (pinfunction "P$66_P$66") (pintype "bidirectional"))
    )
    (net (code "131") (name "unconnected-(CONN1-PadP$67)") (class "Default")
      (node (ref "CONN1") (pin "P$67") (pinfunction "P$67_P$67") (pintype "bidirectional"))
    )
    (net (code "132") (name "unconnected-(CONN1-PadP$68)") (class "Default")
      (node (ref "CONN1") (pin "P$68") (pinfunction "P$68_P$68") (pintype "bidirectional"))
    )
    (net (code "133") (name "unconnected-(CONN1-PadP$73)") (class "Default")
      (node (ref "CONN1") (pin "P$73") (pinfunction "P$73_P$73") (pintype "bidirectional"))
    )
    (net (code "134") (name "unconnected-(CONN1-PadP$74)") (class "Default")
      (node (ref "CONN1") (pin "P$74") (pinfunction "P$74_P$74") (pintype "bidirectional"))
    )
    (net (code "135") (name "unconnected-(CONN1-PadP$75)") (class "Default")
      (node (ref "CONN1") (pin "P$75") (pinfunction "P$75_P$75") (pintype "bidirectional"))
    )
    (net (code "136") (name "unconnected-(CONN1-PadP$76)") (class "Default")
      (node (ref "CONN1") (pin "P$76") (pinfunction "P$76_P$76") (pintype "bidirectional"))
    )
    (net (code "137") (name "unconnected-(CONN1-PadP$81)") (class "Default")
      (node (ref "CONN1") (pin "P$81") (pinfunction "P$81_P$81") (pintype "bidirectional"))
    )
    (net (code "138") (name "unconnected-(CONN1-PadP$82)") (class "Default")
      (node (ref "CONN1") (pin "P$82") (pinfunction "P$82_P$82") (pintype "bidirectional"))
    )
    (net (code "139") (name "unconnected-(CONN1-PadP$83)") (class "Default")
      (node (ref "CONN1") (pin "P$83") (pinfunction "P$83_P$83") (pintype "bidirectional"))
    )
    (net (code "140") (name "unconnected-(CONN1-PadP$84)") (class "Default")
      (node (ref "CONN1") (pin "P$84") (pinfunction "P$84_P$84") (pintype "bidirectional"))
    )
    (net (code "141") (name "unconnected-(CONN1-PadP$89)") (class "Default")
      (node (ref "CONN1") (pin "P$89") (pinfunction "P$89_P$89") (pintype "bidirectional"))
    )
    (net (code "142") (name "unconnected-(CONN1-PadP$90)") (class "Default")
      (node (ref "CONN1") (pin "P$90") (pinfunction "P$90_P$90") (pintype "bidirectional"))
    )
    (net (code "143") (name "unconnected-(CONN1-PadP$91)") (class "Default")
      (node (ref "CONN1") (pin "P$91") (pinfunction "P$91_P$91") (pintype "bidirectional"))
    )
    (net (code "144") (name "unconnected-(CONN1-PadP$92)") (class "Default")
      (node (ref "CONN1") (pin "P$92") (pinfunction "P$92_P$92") (pintype "bidirectional"))
    )
    (net (code "145") (name "unconnected-(CONN1-PadP$95)") (class "Default")
      (node (ref "CONN1") (pin "P$95") (pinfunction "P$95_P$95") (pintype "bidirectional"))
    )
    (net (code "146") (name "unconnected-(CONN1-PadP$96)") (class "Default")
      (node (ref "CONN1") (pin "P$96") (pinfunction "P$96_P$96") (pintype "bidirectional"))
    )
    (net (code "147") (name "unconnected-(CONN1-RAHS_GND-PadP$94)") (class "Default")
      (node (ref "CONN1") (pin "P$94") (pinfunction "RAHS_GND_P$94") (pintype "bidirectional"))
    )
    (net (code "148") (name "unconnected-(CONN1-RAHS_VBAT-PadP$93)") (class "Default")
      (node (ref "CONN1") (pin "P$93") (pinfunction "RAHS_VBAT_P$93") (pintype "bidirectional"))
    )
    (net (code "149") (name "unconnected-(CONN1-TOPDEPLOY+-PadP$51)") (class "Default")
      (node (ref "CONN1") (pin "P$51") (pinfunction "TOPDEPLOY+_P$51") (pintype "bidirectional"))
    )
    (net (code "150") (name "unconnected-(CONN1-TOPDEPLOY+-PadP$55)") (class "Default")
      (node (ref "CONN1") (pin "P$55") (pinfunction "TOPDEPLOY+_P$55") (pintype "bidirectional"))
    )
    (net (code "151") (name "unconnected-(CONN1-TOPDEPLOY-$52-PadP$52)") (class "Default")
      (node (ref "CONN1") (pin "P$52") (pinfunction "TOPDEPLOY-$52_P$52") (pintype "bidirectional"))
    )
    (net (code "152") (name "unconnected-(CONN1-TOPDEPLOY-$56-PadP$56)") (class "Default")
      (node (ref "CONN1") (pin "P$56") (pinfunction "TOPDEPLOY-$56_P$56") (pintype "bidirectional"))
    )
    (net (code "153") (name "unconnected-(CONN1-WHEEL_GND-PadP$71)") (class "Default")
      (node (ref "CONN1") (pin "P$71") (pinfunction "WHEEL_GND_P$71") (pintype "bidirectional"))
    )
    (net (code "154") (name "unconnected-(CONN1-WHEEL_GND-PadP$72)") (class "Default")
      (node (ref "CONN1") (pin "P$72") (pinfunction "WHEEL_GND_P$72") (pintype "bidirectional"))
    )
    (net (code "155") (name "unconnected-(CONN1-WHEEL_VBAT-PadP$69)") (class "Default")
      (node (ref "CONN1") (pin "P$69") (pinfunction "WHEEL_VBAT_P$69") (pintype "bidirectional"))
    )
    (net (code "156") (name "unconnected-(CONN1-WHEEL_VBAT-PadP$70)") (class "Default")
      (node (ref "CONN1") (pin "P$70") (pinfunction "WHEEL_VBAT_P$70") (pintype "bidirectional"))
    )
    (net (code "157") (name "unconnected-(U3-EVENT1{slash}TXD3-PadP$9)") (class "Default")
      (node (ref "U3") (pin "P$9") (pinfunction "EVENT1/TXD3_P$9") (pintype "bidirectional"))
    )
    (net (code "158") (name "unconnected-(U3-EVENT2{slash}CAN1TX-PadP$7)") (class "Default")
      (node (ref "U3") (pin "P$7") (pinfunction "EVENT2/CAN1TX_P$7") (pintype "bidirectional"))
    )
    (net (code "159") (name "unconnected-(U3-NC-PadP$1)") (class "Default")
      (node (ref "U3") (pin "P$1") (pinfunction "NC_P$1") (pintype "bidirectional"))
    )
    (net (code "160") (name "unconnected-(U3-VARF{slash}CAN1RX-PadP$6)") (class "Default")
      (node (ref "U3") (pin "P$6") (pinfunction "VARF/CAN1RX_P$6") (pintype "bidirectional"))
    )
  )
)
